# 2020-03-18_Buck_Regulator.net
KiCad netlist of a schematic drawn in EAGLE
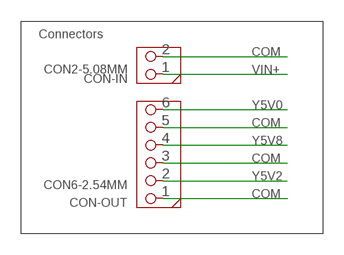
[diagram p0: schematic, sheet 1]
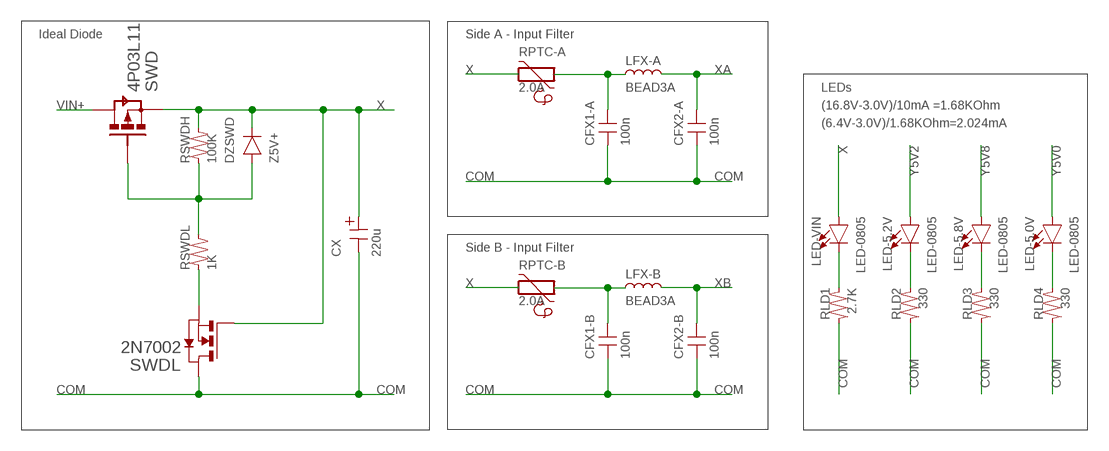
[diagram p1: schematic, sheet 2]
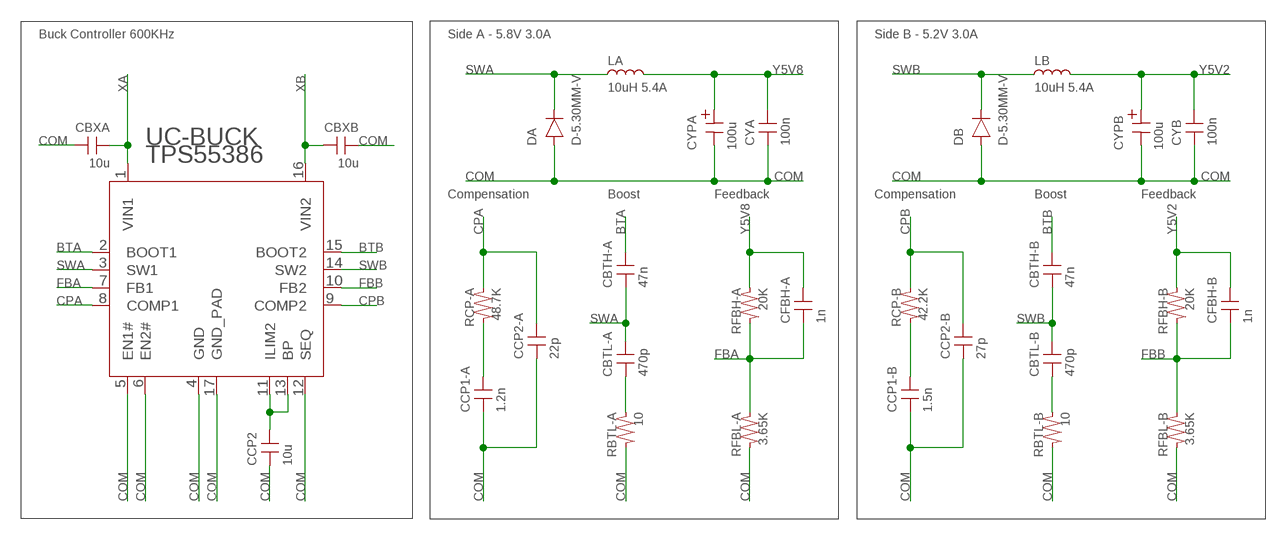
[diagram p2: schematic, sheet 3]
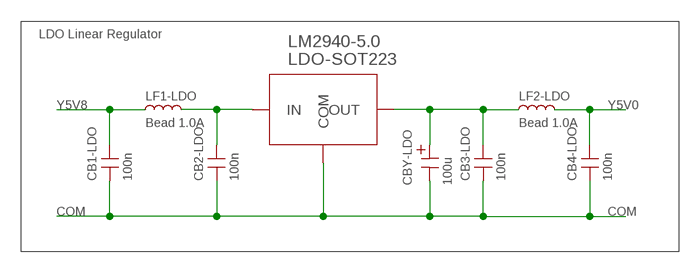
[diagram p3: schematic, sheet 4]

(export (version "E")
  (design (tool "Eeschema 10.0.6"))
  (components
    (comp (ref "CFX1-A")
      (value "100n")
      (footprint "eagle-import:SMD0805")
      (libsource (lib "eagle-import") (part "C-0805"))
    )
    (comp (ref "CFX1-B")
      (value "100n")
      (footprint "eagle-import:SMD0805")
      (libsource (lib "eagle-import") (part "C-0805"))
    )
    (comp (ref "CFX2-A")
      (value "100n")
      (footprint "eagle-import:SMD0805")
      (libsource (lib "eagle-import") (part "C-0805"))
    )
    (comp (ref "CFX2-B")
      (value "100n")
      (footprint "eagle-import:SMD0805")
      (libsource (lib "eagle-import") (part "C-0805"))
    )
    (comp (ref "CX")
      (value "220u")
      (footprint "eagle-import:CPOL-5MM5")
      (libsource (lib "eagle-import") (part "C-POL-5.5MM"))
    )
    (comp (ref "DZSWD")
      (value "Z5V+")
      (footprint "eagle-import:SMD0805-POL")
      (libsource (lib "eagle-import") (part "D-0805"))
    )
    (comp (ref "LED-5.0V")
      (value "LED-0805")
      (footprint "eagle-import:SMD0805-POL")
      (libsource (lib "eagle-import") (part "LED-0805"))
    )
    (comp (ref "LED-5.2V")
      (value "LED-0805")
      (footprint "eagle-import:SMD0805-POL")
      (libsource (lib "eagle-import") (part "LED-0805"))
    )
    (comp (ref "LED-5.8V")
      (value "LED-0805")
      (footprint "eagle-import:SMD0805-POL")
      (libsource (lib "eagle-import") (part "LED-0805"))
    )
    (comp (ref "LED-VIN")
      (value "LED-0805")
      (footprint "eagle-import:SMD0805-POL")
      (libsource (lib "eagle-import") (part "LED-0805"))
    )
    (comp (ref "LFX-A")
      (value "BEAD3A")
      (footprint "eagle-import:SMD2MM0X1MM60")
      (libsource (lib "eagle-import") (part "L-2.0X1.6"))
    )
    (comp (ref "LFX-B")
      (value "BEAD3A")
      (footprint "eagle-import:SMD2MM0X1MM60")
      (libsource (lib "eagle-import") (part "L-2.0X1.6"))
    )
    (comp (ref "RLD1")
      (value "2.7K")
      (footprint "eagle-import:SMD0805")
      (libsource (lib "eagle-import") (part "R"))
    )
    (comp (ref "RLD2")
      (value "330")
      (footprint "eagle-import:SMD0805")
      (libsource (lib "eagle-import") (part "R"))
    )
    (comp (ref "RLD3")
      (value "330")
      (footprint "eagle-import:SMD0805")
      (libsource (lib "eagle-import") (part "R"))
    )
    (comp (ref "RLD4")
      (value "330")
      (footprint "eagle-import:SMD0805")
      (libsource (lib "eagle-import") (part "R"))
    )
    (comp (ref "RPTC-A")
      (value "2.0A")
      (footprint "eagle-import:M0805")
      (libsource (lib "eagle-import") (part "PTC-SMD0805"))
    )
    (comp (ref "RPTC-B")
      (value "2.0A")
      (footprint "eagle-import:M0805")
      (libsource (lib "eagle-import") (part "PTC-SMD0805"))
    )
    (comp (ref "RSWDH")
      (value "100K")
      (footprint "eagle-import:SMD0805")
      (libsource (lib "eagle-import") (part "R"))
    )
    (comp (ref "RSWDL")
      (value "1K")
      (footprint "eagle-import:SMD0805")
      (libsource (lib "eagle-import") (part "R"))
    )
    (comp (ref "SWD")
      (value "4P03L11")
      (footprint "eagle-import:TO252")
      (libsource (lib "eagle-import") (part "PMOSTO252"))
    )
    (comp (ref "SWDL")
      (value "2N7002")
      (footprint "eagle-import:SOT23")
      (libsource (lib "eagle-import") (part "NMOS-SOT23"))
    )
    (comp (ref "CBTH-A")
      (value "47n")
      (footprint "eagle-import:SMD0805")
      (libsource (lib "eagle-import") (part "C-0805"))
    )
    (comp (ref "CBTH-B")
      (value "47n")
      (footprint "eagle-import:SMD0805")
      (libsource (lib "eagle-import") (part "C-0805"))
    )
    (comp (ref "CBTL-A")
      (value "470p")
      (footprint "eagle-import:SMD0805")
      (libsource (lib "eagle-import") (part "C-0805"))
    )
    (comp (ref "CBTL-B")
      (value "470p")
      (footprint "eagle-import:SMD0805")
      (libsource (lib "eagle-import") (part "C-0805"))
    )
    (comp (ref "CBXA")
      (value "10u")
      (footprint "eagle-import:SMD3MM2X1MM60")
      (libsource (lib "eagle-import") (part "C-1206"))
    )
    (comp (ref "CBXB")
      (value "10u")
      (footprint "eagle-import:SMD3MM2X1MM60")
      (libsource (lib "eagle-import") (part "C-1206"))
    )
    (comp (ref "CCP1-A")
      (value "1.2n")
      (footprint "eagle-import:SMD0805")
      (libsource (lib "eagle-import") (part "C-0805"))
    )
    (comp (ref "CCP1-B")
      (value "1.5n")
      (footprint "eagle-import:SMD0805")
      (libsource (lib "eagle-import") (part "C-0805"))
    )
    (comp (ref "CCP2")
      (value "10u")
      (footprint "eagle-import:SMD3MM2X1MM60")
      (libsource (lib "eagle-import") (part "C-1206"))
    )
    (comp (ref "CCP2-A")
      (value "22p")
      (footprint "eagle-import:SMD0805")
      (libsource (lib "eagle-import") (part "C-0805"))
    )
    (comp (ref "CCP2-B")
      (value "27p")
      (footprint "eagle-import:SMD0805")
      (libsource (lib "eagle-import") (part "C-0805"))
    )
    (comp (ref "CFBH-A")
      (value "1n")
      (footprint "eagle-import:SMD0805")
      (libsource (lib "eagle-import") (part "C-0805"))
    )
    (comp (ref "CFBH-B")
      (value "1n")
      (footprint "eagle-import:SMD0805")
      (libsource (lib "eagle-import") (part "C-0805"))
    )
    (comp (ref "CYA")
      (value "100n")
      (footprint "eagle-import:SMD0805")
      (libsource (lib "eagle-import") (part "C-0805"))
    )
    (comp (ref "CYB")
      (value "100n")
      (footprint "eagle-import:SMD0805")
      (libsource (lib "eagle-import") (part "C-0805"))
    )
    (comp (ref "CYPA")
      (value "100u")
      (footprint "eagle-import:CPOL-5MM5")
      (libsource (lib "eagle-import") (part "C-POL-5.5MM"))
    )
    (comp (ref "CYPB")
      (value "100u")
      (footprint "eagle-import:CPOL-5MM5")
      (libsource (lib "eagle-import") (part "C-POL-5.5MM"))
    )
    (comp (ref "DA")
      (value "D-5.30MM-V")
      (footprint "eagle-import:THV-5MM30")
      (libsource (lib "eagle-import") (part "D-5.30MM-V"))
    )
    (comp (ref "DB")
      (value "D-5.30MM-V")
      (footprint "eagle-import:THV-5MM30")
      (libsource (lib "eagle-import") (part "D-5.30MM-V"))
    )
    (comp (ref "LA")
      (value "10uH 5.4A")
      (footprint "eagle-import:SMD12MM8X12MM8")
      (libsource (lib "eagle-import") (part "L-12.8X12.8"))
    )
    (comp (ref "LB")
      (value "10uH 5.4A")
      (footprint "eagle-import:SMD12MM8X12MM8")
      (libsource (lib "eagle-import") (part "L-12.8X12.8"))
    )
    (comp (ref "RBTL-A")
      (value "10")
      (footprint "eagle-import:SMD0805")
      (libsource (lib "eagle-import") (part "R"))
    )
    (comp (ref "RBTL-B")
      (value "10")
      (footprint "eagle-import:SMD0805")
      (libsource (lib "eagle-import") (part "R"))
    )
    (comp (ref "RCP-A")
      (value "48.7K")
      (footprint "eagle-import:SMD0805")
      (libsource (lib "eagle-import") (part "R"))
    )
    (comp (ref "RCP-B")
      (value "42.2K")
      (footprint "eagle-import:SMD0805")
      (libsource (lib "eagle-import") (part "R"))
    )
    (comp (ref "RFBH-A")
      (value "20K")
      (footprint "eagle-import:SMD0805")
      (libsource (lib "eagle-import") (part "R"))
    )
    (comp (ref "RFBH-B")
      (value "20K")
      (footprint "eagle-import:SMD0805")
      (libsource (lib "eagle-import") (part "R"))
    )
    (comp (ref "RFBL-A")
      (value "3.65K")
      (footprint "eagle-import:SMD0805")
      (libsource (lib "eagle-import") (part "R"))
    )
    (comp (ref "RFBL-B")
      (value "3.65K")
      (footprint "eagle-import:SMD0805")
      (libsource (lib "eagle-import") (part "R"))
    )
    (comp (ref "UC-BUCK")
      (value "TPS55386")
      (footprint "eagle-import:HTSSOP16")
      (libsource (lib "eagle-import") (part "TPS55386"))
    )
    (comp (ref "CON-IN")
      (value "CON2-5.08MM")
      (footprint "eagle-import:CON2-508")
      (libsource (lib "eagle-import") (part "CON2-5.08MM"))
    )
    (comp (ref "CON-OUT")
      (value "CON6-2.54MM")
      (footprint "eagle-import:CON6")
      (libsource (lib "eagle-import") (part "CON6-2.54MM"))
    )
    (comp (ref "CB1-LDO")
      (value "100n")
      (footprint "eagle-import:SMD0805")
      (libsource (lib "eagle-import") (part "C-0805"))
    )
    (comp (ref "CB2-LDO")
      (value "100n")
      (footprint "eagle-import:SMD0805")
      (libsource (lib "eagle-import") (part "C-0805"))
    )
    (comp (ref "CB3-LDO")
      (value "100n")
      (footprint "eagle-import:SMD0805")
      (libsource (lib "eagle-import") (part "C-0805"))
    )
    (comp (ref "CB4-LDO")
      (value "100n")
      (footprint "eagle-import:SMD0805")
      (libsource (lib "eagle-import") (part "C-0805"))
    )
    (comp (ref "CBY-LDO")
      (value "100u")
      (footprint "eagle-import:CPOL-5MM5")
      (libsource (lib "eagle-import") (part "C-POL-5.5MM"))
    )
    (comp (ref "LF1-LDO")
      (value "Bead 1.0A")
      (footprint "eagle-import:SMD0805")
      (libsource (lib "eagle-import") (part "L-0805"))
    )
    (comp (ref "LF2-LDO")
      (value "Bead 1.0A")
      (footprint "eagle-import:SMD0805")
      (libsource (lib "eagle-import") (part "L-0805"))
    )
    (comp (ref "LM2940-5.0")
      (value "LDO-SOT223")
      (footprint "eagle-import:SOT223")
      (libsource (lib "eagle-import") (part "LDO-SOT223"))
    )
  )
  (nets
    (net (code "1") (name "BTA") (class "Default")
      (node (ref "CBTH-A") (pin "1") (pinfunction "1_1") (pintype "bidirectional"))
      (node (ref "UC-BUCK") (pin "2") (pinfunction "BOOT1_2") (pintype "bidirectional"))
    )
    (net (code "2") (name "BTB") (class "Default")
      (node (ref "CBTH-B") (pin "1") (pinfunction "1_1") (pintype "bidirectional"))
      (node (ref "UC-BUCK") (pin "15") (pinfunction "BOOT2_15") (pintype "bidirectional"))
    )
    (net (code "3") (name "COM") (class "Default")
      (node (ref "CB1-LDO") (pin "2") (pinfunction "2_2") (pintype "bidirectional"))
      (node (ref "CB2-LDO") (pin "2") (pinfunction "2_2") (pintype "bidirectional"))
      (node (ref "CB3-LDO") (pin "2") (pinfunction "2_2") (pintype "bidirectional"))
      (node (ref "CB4-LDO") (pin "2") (pinfunction "2_2") (pintype "bidirectional"))
      (node (ref "CBXA") (pin "1") (pinfunction "1_1") (pintype "bidirectional"))
      (node (ref "CBXB") (pin "2") (pinfunction "2_2") (pintype "bidirectional"))
      (node (ref "CBY-LDO") (pin "-") (pinfunction "-_-") (pintype "bidirectional"))
      (node (ref "CCP1-A") (pin "2") (pinfunction "2_2") (pintype "bidirectional"))
      (node (ref "CCP1-B") (pin "2") (pinfunction "2_2") (pintype "bidirectional"))
      (node (ref "CCP2") (pin "2") (pinfunction "2_2") (pintype "bidirectional"))
      (node (ref "CCP2-A") (pin "2") (pinfunction "2_2") (pintype "bidirectional"))
      (node (ref "CCP2-B") (pin "2") (pinfunction "2_2") (pintype "bidirectional"))
      (node (ref "CFX1-A") (pin "2") (pinfunction "2_2") (pintype "bidirectional"))
      (node (ref "CFX1-B") (pin "2") (pinfunction "2_2") (pintype "bidirectional"))
      (node (ref "CFX2-A") (pin "2") (pinfunction "2_2") (pintype "bidirectional"))
      (node (ref "CFX2-B") (pin "2") (pinfunction "2_2") (pintype "bidirectional"))
      (node (ref "CON-IN") (pin "2") (pinfunction "2_2") (pintype "passive"))
      (node (ref "CON-OUT") (pin "1") (pinfunction "1_1") (pintype "passive"))
      (node (ref "CON-OUT") (pin "3") (pinfunction "3_3") (pintype "passive"))
      (node (ref "CON-OUT") (pin "5") (pinfunction "5_5") (pintype "passive"))
      (node (ref "CX") (pin "-") (pinfunction "-_-") (pintype "bidirectional"))
      (node (ref "CYA") (pin "2") (pinfunction "2_2") (pintype "bidirectional"))
      (node (ref "CYB") (pin "2") (pinfunction "2_2") (pintype "bidirectional"))
      (node (ref "CYPA") (pin "-") (pinfunction "-_-") (pintype "bidirectional"))
      (node (ref "CYPB") (pin "-") (pinfunction "-_-") (pintype "bidirectional"))
      (node (ref "DA") (pin "+") (pinfunction "+_+") (pintype "passive"))
      (node (ref "DB") (pin "+") (pinfunction "+_+") (pintype "passive"))
      (node (ref "LM2940-5.0") (pin "2") (pinfunction "COM_2") (pintype "passive"))
      (node (ref "LM2940-5.0") (pin "4") (pinfunction "COM_4") (pintype "passive"))
      (node (ref "RBTL-A") (pin "2") (pinfunction "P$2_2") (pintype "bidirectional"))
      (node (ref "RBTL-B") (pin "2") (pinfunction "P$2_2") (pintype "bidirectional"))
      (node (ref "RFBL-A") (pin "2") (pinfunction "P$2_2") (pintype "bidirectional"))
      (node (ref "RFBL-B") (pin "2") (pinfunction "P$2_2") (pintype "bidirectional"))
      (node (ref "RLD1") (pin "2") (pinfunction "P$2_2") (pintype "bidirectional"))
      (node (ref "RLD2") (pin "2") (pinfunction "P$2_2") (pintype "bidirectional"))
      (node (ref "RLD3") (pin "2") (pinfunction "P$2_2") (pintype "bidirectional"))
      (node (ref "RLD4") (pin "2") (pinfunction "P$2_2") (pintype "bidirectional"))
      (node (ref "SWDL") (pin "3") (pinfunction "D_3") (pintype "passive"))
      (node (ref "UC-BUCK") (pin "12") (pinfunction "SEQ_12") (pintype "bidirectional"))
      (node (ref "UC-BUCK") (pin "17") (pinfunction "GND_PAD_17") (pintype "bidirectional"))
      (node (ref "UC-BUCK") (pin "4") (pinfunction "GND_4") (pintype "bidirectional"))
      (node (ref "UC-BUCK") (pin "5") (pinfunction "EN1#_5") (pintype "bidirectional"))
      (node (ref "UC-BUCK") (pin "6") (pinfunction "EN2#_6") (pintype "bidirectional"))
    )
    (net (code "4") (name "CPA") (class "Default")
      (node (ref "CCP2-A") (pin "1") (pinfunction "1_1") (pintype "bidirectional"))
      (node (ref "RCP-A") (pin "1") (pinfunction "P$1_1") (pintype "bidirectional"))
      (node (ref "UC-BUCK") (pin "8") (pinfunction "COMP1_8") (pintype "bidirectional"))
    )
    (net (code "5") (name "CPB") (class "Default")
      (node (ref "CCP2-B") (pin "1") (pinfunction "1_1") (pintype "bidirectional"))
      (node (ref "RCP-B") (pin "1") (pinfunction "P$1_1") (pintype "bidirectional"))
      (node (ref "UC-BUCK") (pin "9") (pinfunction "COMP2_9") (pintype "bidirectional"))
    )
    (net (code "6") (name "FBA") (class "Default")
      (node (ref "CFBH-A") (pin "2") (pinfunction "2_2") (pintype "bidirectional"))
      (node (ref "RFBH-A") (pin "2") (pinfunction "P$2_2") (pintype "bidirectional"))
      (node (ref "RFBL-A") (pin "1") (pinfunction "P$1_1") (pintype "bidirectional"))
      (node (ref "UC-BUCK") (pin "7") (pinfunction "FB1_7") (pintype "bidirectional"))
    )
    (net (code "7") (name "FBB") (class "Default")
      (node (ref "CFBH-B") (pin "2") (pinfunction "2_2") (pintype "bidirectional"))
      (node (ref "RFBH-B") (pin "2") (pinfunction "P$2_2") (pintype "bidirectional"))
      (node (ref "RFBL-B") (pin "1") (pinfunction "P$1_1") (pintype "bidirectional"))
      (node (ref "UC-BUCK") (pin "10") (pinfunction "FB2_10") (pintype "bidirectional"))
    )
    (net (code "8") (name "Net-(CFX1-A-Pad1)") (class "Default")
      (node (ref "CFX1-A") (pin "1") (pinfunction "1_1") (pintype "bidirectional"))
      (node (ref "LFX-A") (pin "1") (pinfunction "1_1") (pintype "passive"))
      (node (ref "RPTC-A") (pin "2") (pinfunction "2_2") (pintype "passive"))
    )
    (net (code "9") (name "Net-(CFX1-B-Pad1)") (class "Default")
      (node (ref "CFX1-B") (pin "1") (pinfunction "1_1") (pintype "bidirectional"))
      (node (ref "LFX-B") (pin "1") (pinfunction "1_1") (pintype "passive"))
      (node (ref "RPTC-B") (pin "2") (pinfunction "2_2") (pintype "passive"))
    )
    (net (code "10") (name "Net-(LM2940-5.0-IN)") (class "Default")
      (node (ref "CB2-LDO") (pin "1") (pinfunction "1_1") (pintype "bidirectional"))
      (node (ref "LF1-LDO") (pin "2") (pinfunction "2_2") (pintype "passive"))
      (node (ref "LM2940-5.0") (pin "1") (pinfunction "IN_1") (pintype "passive"))
    )
    (net (code "11") (name "Net-(LM2940-5.0-OUT)") (class "Default")
      (node (ref "CB3-LDO") (pin "1") (pinfunction "1_1") (pintype "bidirectional"))
      (node (ref "CBY-LDO") (pin "+") (pinfunction "+_+") (pintype "bidirectional"))
      (node (ref "LF2-LDO") (pin "1") (pinfunction "1_1") (pintype "passive"))
      (node (ref "LM2940-5.0") (pin "3") (pinfunction "OUT_3") (pintype "passive"))
    )
    (net (code "12") (name "Net-(RBTL-A-P$1)") (class "Default")
      (node (ref "CBTL-A") (pin "2") (pinfunction "2_2") (pintype "bidirectional"))
      (node (ref "RBTL-A") (pin "1") (pinfunction "P$1_1") (pintype "bidirectional"))
    )
    (net (code "13") (name "Net-(RBTL-B-P$1)") (class "Default")
      (node (ref "CBTL-B") (pin "2") (pinfunction "2_2") (pintype "bidirectional"))
      (node (ref "RBTL-B") (pin "1") (pinfunction "P$1_1") (pintype "bidirectional"))
    )
    (net (code "14") (name "Net-(RCP-A-P$2)") (class "Default")
      (node (ref "CCP1-A") (pin "1") (pinfunction "1_1") (pintype "bidirectional"))
      (node (ref "RCP-A") (pin "2") (pinfunction "P$2_2") (pintype "bidirectional"))
    )
    (net (code "15") (name "Net-(RCP-B-P$2)") (class "Default")
      (node (ref "CCP1-B") (pin "1") (pinfunction "1_1") (pintype "bidirectional"))
      (node (ref "RCP-B") (pin "2") (pinfunction "P$2_2") (pintype "bidirectional"))
    )
    (net (code "16") (name "Net-(RLD1-P$1)") (class "Default")
      (node (ref "LED-VIN") (pin "-") (pinfunction "-_-") (pintype "passive"))
      (node (ref "RLD1") (pin "1") (pinfunction "P$1_1") (pintype "bidirectional"))
    )
    (net (code "17") (name "Net-(RLD2-P$1)") (class "Default")
      (node (ref "LED-5.2V") (pin "-") (pinfunction "-_-") (pintype "passive"))
      (node (ref "RLD2") (pin "1") (pinfunction "P$1_1") (pintype "bidirectional"))
    )
    (net (code "18") (name "Net-(RLD3-P$1)") (class "Default")
      (node (ref "LED-5.8V") (pin "-") (pinfunction "-_-") (pintype "passive"))
      (node (ref "RLD3") (pin "1") (pinfunction "P$1_1") (pintype "bidirectional"))
    )
    (net (code "19") (name "Net-(RLD4-P$1)") (class "Default")
      (node (ref "LED-5.0V") (pin "-") (pinfunction "-_-") (pintype "passive"))
      (node (ref "RLD4") (pin "1") (pinfunction "P$1_1") (pintype "bidirectional"))
    )
    (net (code "20") (name "Net-(RSWDH-P$1)") (class "Default")
      (node (ref "DZSWD") (pin "+") (pinfunction "+_+") (pintype "passive"))
      (node (ref "RSWDH") (pin "1") (pinfunction "P$1_1") (pintype "bidirectional"))
      (node (ref "RSWDL") (pin "2") (pinfunction "P$2_2") (pintype "bidirectional"))
      (node (ref "SWD") (pin "1") (pinfunction "G_1") (pintype "passive"))
    )
    (net (code "21") (name "Net-(RSWDL-P$1)") (class "Default")
      (node (ref "RSWDL") (pin "1") (pinfunction "P$1_1") (pintype "bidirectional"))
      (node (ref "SWDL") (pin "2") (pinfunction "S_2") (pintype "passive"))
    )
    (net (code "22") (name "Net-(UC-BUCK-BP)") (class "Default")
      (node (ref "CCP2") (pin "1") (pinfunction "1_1") (pintype "bidirectional"))
      (node (ref "UC-BUCK") (pin "11") (pinfunction "ILIM2_11") (pintype "bidirectional"))
      (node (ref "UC-BUCK") (pin "13") (pinfunction "BP_13") (pintype "bidirectional"))
    )
    (net (code "23") (name "SWA") (class "Default")
      (node (ref "CBTH-A") (pin "2") (pinfunction "2_2") (pintype "bidirectional"))
      (node (ref "CBTL-A") (pin "1") (pinfunction "1_1") (pintype "bidirectional"))
      (node (ref "DA") (pin "-") (pinfunction "-_-") (pintype "passive"))
      (node (ref "LA") (pin "1") (pinfunction "1_1") (pintype "passive"))
      (node (ref "UC-BUCK") (pin "3") (pinfunction "SW1_3") (pintype "bidirectional"))
    )
    (net (code "24") (name "SWB") (class "Default")
      (node (ref "CBTH-B") (pin "2") (pinfunction "2_2") (pintype "bidirectional"))
      (node (ref "CBTL-B") (pin "1") (pinfunction "1_1") (pintype "bidirectional"))
      (node (ref "DB") (pin "-") (pinfunction "-_-") (pintype "passive"))
      (node (ref "LB") (pin "1") (pinfunction "1_1") (pintype "passive"))
      (node (ref "UC-BUCK") (pin "14") (pinfunction "SW2_14") (pintype "bidirectional"))
    )
    (net (code "25") (name "VIN+") (class "Default")
      (node (ref "CON-IN") (pin "1") (pinfunction "1_1") (pintype "passive"))
      (node (ref "SWD") (pin "3") (pinfunction "D_3") (pintype "passive"))
    )
    (net (code "26") (name "X") (class "Default")
      (node (ref "CX") (pin "+") (pinfunction "+_+") (pintype "bidirectional"))
      (node (ref "DZSWD") (pin "-") (pinfunction "-_-") (pintype "passive"))
      (node (ref "LED-VIN") (pin "+") (pinfunction "+_+") (pintype "passive"))
      (node (ref "RPTC-A") (pin "1") (pinfunction "1_1") (pintype "passive"))
      (node (ref "RPTC-B") (pin "1") (pinfunction "1_1") (pintype "passive"))
      (node (ref "RSWDH") (pin "2") (pinfunction "P$2_2") (pintype "bidirectional"))
      (node (ref "SWD") (pin "2") (pinfunction "S_2") (pintype "passive"))
      (node (ref "SWDL") (pin "1") (pinfunction "G_1") (pintype "passive"))
    )
    (net (code "27") (name "XA") (class "Default")
      (node (ref "CBXA") (pin "2") (pinfunction "2_2") (pintype "bidirectional"))
      (node (ref "CFX2-A") (pin "1") (pinfunction "1_1") (pintype "bidirectional"))
      (node (ref "LFX-A") (pin "2") (pinfunction "2_2") (pintype "passive"))
      (node (ref "UC-BUCK") (pin "1") (pinfunction "VIN1_1") (pintype "bidirectional"))
    )
    (net (code "28") (name "XB") (class "Default")
      (node (ref "CBXB") (pin "1") (pinfunction "1_1") (pintype "bidirectional"))
      (node (ref "CFX2-B") (pin "1") (pinfunction "1_1") (pintype "bidirectional"))
      (node (ref "LFX-B") (pin "2") (pinfunction "2_2") (pintype "passive"))
      (node (ref "UC-BUCK") (pin "16") (pinfunction "VIN2_16") (pintype "bidirectional"))
    )
    (net (code "29") (name "Y5V0") (class "Default")
      (node (ref "CB4-LDO") (pin "1") (pinfunction "1_1") (pintype "bidirectional"))
      (node (ref "CON-OUT") (pin "6") (pinfunction "6_6") (pintype "passive"))
      (node (ref "LED-5.0V") (pin "+") (pinfunction "+_+") (pintype "passive"))
      (node (ref "LF2-LDO") (pin "2") (pinfunction "2_2") (pintype "passive"))
    )
    (net (code "30") (name "Y5V2") (class "Default")
      (node (ref "CFBH-B") (pin "1") (pinfunction "1_1") (pintype "bidirectional"))
      (node (ref "CON-OUT") (pin "2") (pinfunction "2_2") (pintype "passive"))
      (node (ref "CYB") (pin "1") (pinfunction "1_1") (pintype "bidirectional"))
      (node (ref "CYPB") (pin "+") (pinfunction "+_+") (pintype "bidirectional"))
      (node (ref "LB") (pin "2") (pinfunction "2_2") (pintype "passive"))
      (node (ref "LED-5.2V") (pin "+") (pinfunction "+_+") (pintype "passive"))
      (node (ref "RFBH-B") (pin "1") (pinfunction "P$1_1") (pintype "bidirectional"))
    )
    (net (code "31") (name "Y5V8") (class "Default")
      (node (ref "CB1-LDO") (pin "1") (pinfunction "1_1") (pintype "bidirectional"))
      (node (ref "CFBH-A") (pin "1") (pinfunction "1_1") (pintype "bidirectional"))
      (node (ref "CON-OUT") (pin "4") (pinfunction "4_4") (pintype "passive"))
      (node (ref "CYA") (pin "1") (pinfunction "1_1") (pintype "bidirectional"))
      (node (ref "CYPA") (pin "+") (pinfunction "+_+") (pintype "bidirectional"))
      (node (ref "LA") (pin "2") (pinfunction "2_2") (pintype "passive"))
      (node (ref "LED-5.8V") (pin "+") (pinfunction "+_+") (pintype "passive"))
      (node (ref "LF1-LDO") (pin "1") (pinfunction "1_1") (pintype "passive"))
      (node (ref "RFBH-A") (pin "1") (pinfunction "P$1_1") (pintype "bidirectional"))
    )
  )
)
